# TakpadV6_1.net
KiCad netlist of a schematic drawn in EAGLE
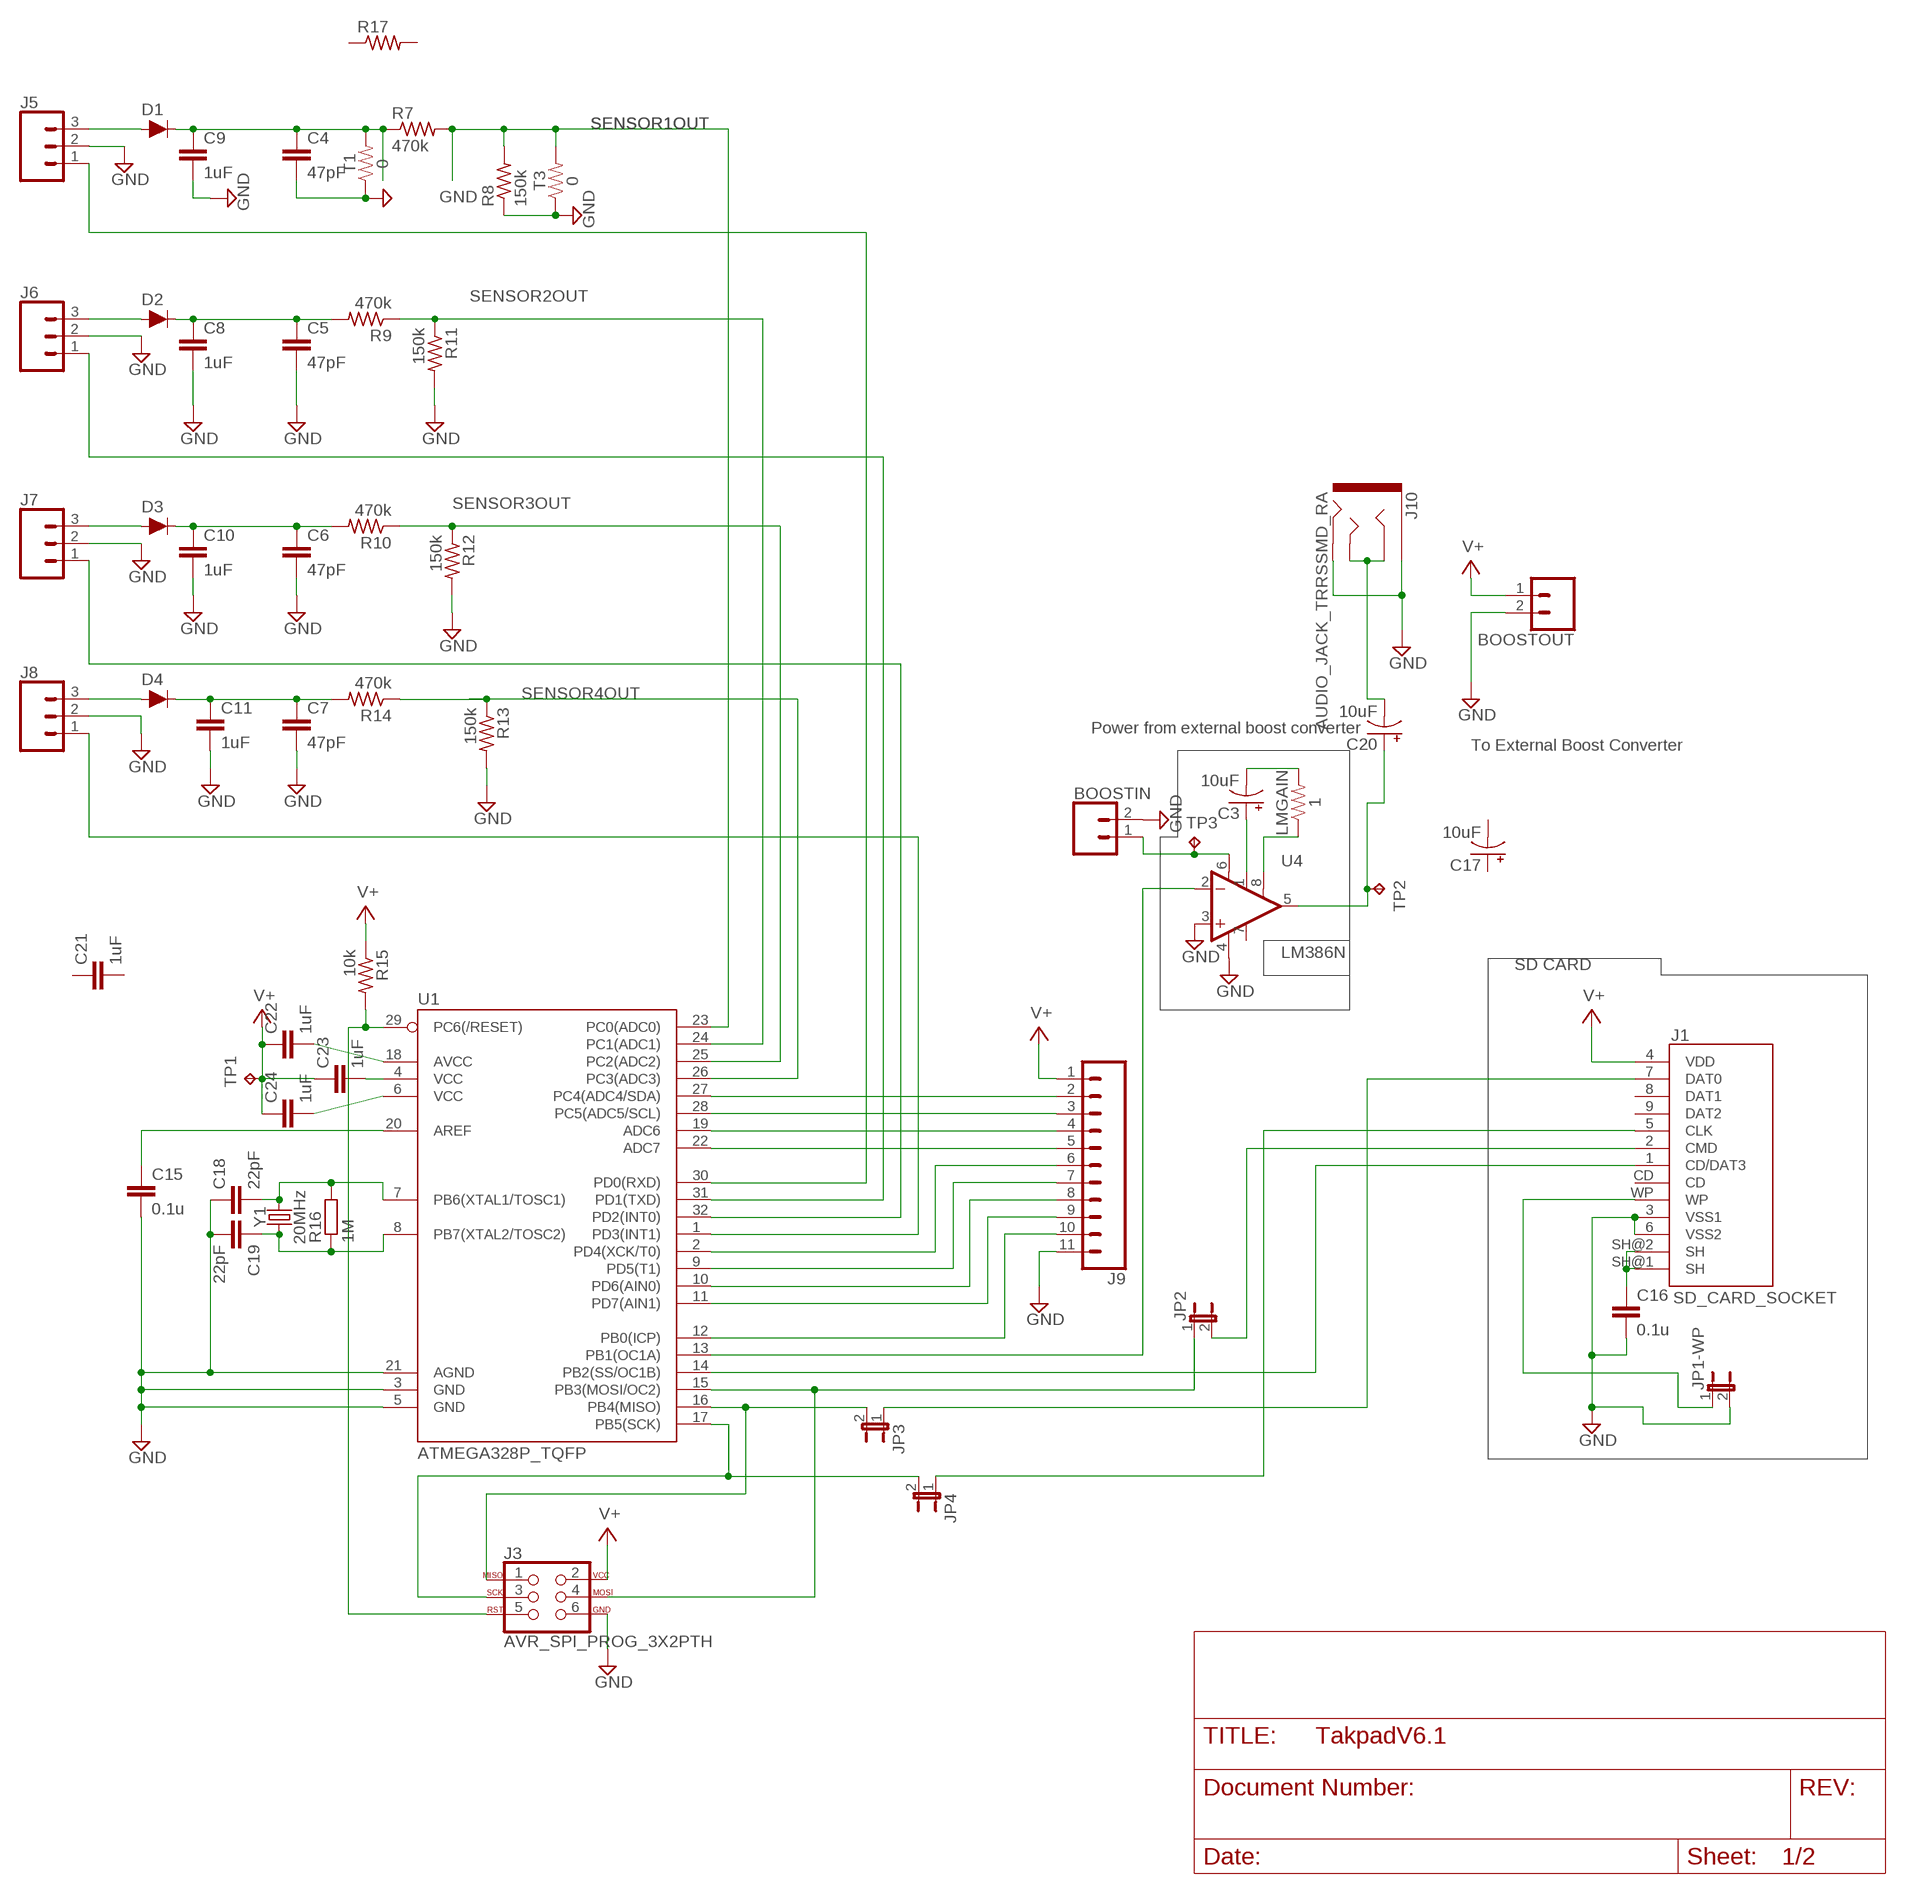
[diagram p0: schematic, sheet 1]
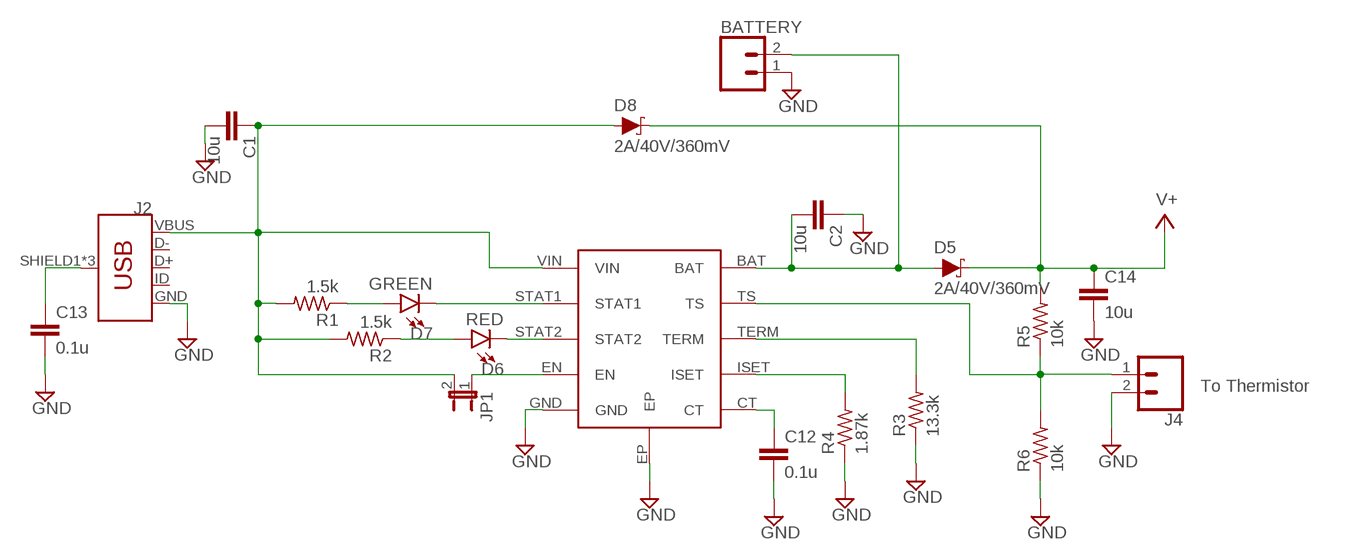
[diagram p1: schematic, sheet 2]

(export (version "E")
  (design (tool "Eeschema 10.0.6"))
  (components
    (comp (ref "BATTERY")
      (value "CONN_02")
      (footprint "eagle-import:1X02")
      (libsource (lib "eagle-import") (part "CONN_02"))
    )
    (comp (ref "C1")
      (value "10u")
      (footprint "eagle-import:C0402")
      (libsource (lib "eagle-import") (part "C-EUC0402"))
    )
    (comp (ref "C2")
      (value "10u")
      (footprint "eagle-import:C0402")
      (libsource (lib "eagle-import") (part "C-EUC0402"))
    )
    (comp (ref "C12")
      (value "0.1u")
      (footprint "eagle-import:C0402")
      (libsource (lib "eagle-import") (part "C-EUC0402"))
    )
    (comp (ref "C13")
      (value "0.1u")
      (footprint "eagle-import:C0402")
      (libsource (lib "eagle-import") (part "C-EUC0402"))
    )
    (comp (ref "C14")
      (value "10u")
      (footprint "eagle-import:C0402")
      (libsource (lib "eagle-import") (part "C-EUC0402"))
    )
    (comp (ref "D5")
      (value "2A/40V/360mV")
      (footprint "eagle-import:SMA-DIODE")
      (libsource (lib "eagle-import") (part "DIODE-SCHOTTKY-B340A"))
    )
    (comp (ref "D6")
      (value "RED")
      (footprint "eagle-import:LED-1206")
      (libsource (lib "eagle-import") (part "LED-RED1206"))
    )
    (comp (ref "D7")
      (value "GREEN")
      (footprint "eagle-import:LED-1206")
      (libsource (lib "eagle-import") (part "LED-GREEN1206"))
    )
    (comp (ref "D8")
      (value "2A/40V/360mV")
      (footprint "eagle-import:SMA-DIODE")
      (libsource (lib "eagle-import") (part "DIODE-SCHOTTKY-B340A"))
    )
    (comp (ref "J2")
      (value "USB_MICRO-BREDUCED_PASTE")
      (footprint "eagle-import:USB-B-MICRO-SMD_RED_PASTE")
      (libsource (lib "eagle-import") (part "USB_MICRO-BREDUCED_PASTE"))
    )
    (comp (ref "J4")
      (value "CONN_02")
      (footprint "eagle-import:1X02")
      (libsource (lib "eagle-import") (part "CONN_02"))
    )
    (comp (ref "JP1")
      (value "JUMPER-2PTH")
      (footprint "eagle-import:1X02")
      (libsource (lib "eagle-import") (part "JUMPER-2PTH"))
    )
    (comp (ref "R1")
      (value "1.5k")
      (footprint "eagle-import:M1206")
      (libsource (lib "eagle-import") (part "R-US_M1206"))
    )
    (comp (ref "R2")
      (value "1.5k")
      (footprint "eagle-import:M1206")
      (libsource (lib "eagle-import") (part "R-US_M1206"))
    )
    (comp (ref "R3")
      (value "13.3k")
      (footprint "eagle-import:M1206")
      (libsource (lib "eagle-import") (part "R-US_M1206"))
    )
    (comp (ref "R4")
      (value "1.87k")
      (footprint "eagle-import:M1206")
      (libsource (lib "eagle-import") (part "R-US_M1206"))
    )
    (comp (ref "R5")
      (value "10k")
      (footprint "eagle-import:M1206")
      (libsource (lib "eagle-import") (part "R-US_M1206"))
    )
    (comp (ref "R6")
      (value "10k")
      (footprint "eagle-import:M1206")
      (libsource (lib "eagle-import") (part "R-US_M1206"))
    )
    (comp (ref "U$1")
      (value "AAT3693")
      (footprint "eagle-import:IDH-AA-T1")
      (libsource (lib "eagle-import") (part "AAT3693"))
    )
    (comp (ref "BOOSTIN")
      (value "CONN_02")
      (footprint "eagle-import:1X02")
      (libsource (lib "eagle-import") (part "CONN_02"))
    )
    (comp (ref "BOOSTOUT")
      (value "CONN_02")
      (footprint "eagle-import:1X02")
      (libsource (lib "eagle-import") (part "CONN_02"))
    )
    (comp (ref "C3")
      (value "10uF")
      (footprint "eagle-import:CPOL-RADIAL-2.5MM-5MM-KIT")
      (libsource (lib "eagle-import") (part "10UF-POLAR-RADIAL-2.5MM-KIT-25V-20%"))
    )
    (comp (ref "C4")
      (value "47pF")
      (footprint "eagle-import:0603")
      (libsource (lib "eagle-import") (part "47PF-0603-50V-5%"))
    )
    (comp (ref "C5")
      (value "47pF")
      (footprint "eagle-import:0603")
      (libsource (lib "eagle-import") (part "47PF-0603-50V-5%"))
    )
    (comp (ref "C6")
      (value "47pF")
      (footprint "eagle-import:0603")
      (libsource (lib "eagle-import") (part "47PF-0603-50V-5%"))
    )
    (comp (ref "C7")
      (value "47pF")
      (footprint "eagle-import:0603")
      (libsource (lib "eagle-import") (part "47PF-0603-50V-5%"))
    )
    (comp (ref "C8")
      (value "1uF")
      (footprint "eagle-import:0603")
      (libsource (lib "eagle-import") (part "47PF-0603-50V-5%"))
    )
    (comp (ref "C9")
      (value "1uF")
      (footprint "eagle-import:0603")
      (libsource (lib "eagle-import") (part "47PF-0603-50V-5%"))
    )
    (comp (ref "C10")
      (value "1uF")
      (footprint "eagle-import:0603")
      (libsource (lib "eagle-import") (part "47PF-0603-50V-5%"))
    )
    (comp (ref "C11")
      (value "1uF")
      (footprint "eagle-import:0603")
      (libsource (lib "eagle-import") (part "47PF-0603-50V-5%"))
    )
    (comp (ref "C15")
      (value "0.1u")
      (footprint "eagle-import:C0402")
      (libsource (lib "eagle-import") (part "C-EUC0402"))
    )
    (comp (ref "C16")
      (value "0.1u")
      (footprint "eagle-import:C0402")
      (libsource (lib "eagle-import") (part "C-EUC0402"))
    )
    (comp (ref "C17")
      (value "10uF")
      (footprint "eagle-import:CPOL-RADIAL-2.5MM-5MM-KIT")
      (libsource (lib "eagle-import") (part "10UF-POLAR-RADIAL-2.5MM-KIT-25V-20%"))
    )
    (comp (ref "C18")
      (value "22pF")
      (footprint "eagle-import:C0402")
      (libsource (lib "eagle-import") (part "resistor_348_C-EUC0402"))
    )
    (comp (ref "C19")
      (value "22pF")
      (footprint "eagle-import:C0402")
      (libsource (lib "eagle-import") (part "resistor_348_C-EUC0402"))
    )
    (comp (ref "C20")
      (value "10uF")
      (footprint "eagle-import:CPOL-RADIAL-2.5MM-5MM-KIT")
      (libsource (lib "eagle-import") (part "10UF-POLAR-RADIAL-2.5MM-KIT-25V-20%"))
    )
    (comp (ref "C21")
      (value "1uF")
      (footprint "eagle-import:0603")
      (libsource (lib "eagle-import") (part "47PF-0603-50V-5%"))
    )
    (comp (ref "C22")
      (value "1uF")
      (footprint "eagle-import:0603")
      (libsource (lib "eagle-import") (part "47PF-0603-50V-5%"))
    )
    (comp (ref "C23")
      (value "1uF")
      (footprint "eagle-import:0603")
      (libsource (lib "eagle-import") (part "47PF-0603-50V-5%"))
    )
    (comp (ref "C24")
      (value "1uF")
      (footprint "eagle-import:0603")
      (libsource (lib "eagle-import") (part "47PF-0603-50V-5%"))
    )
    (comp (ref "D1")
      (value "200mA/100V/1V")
      (footprint "eagle-import:DIODE-1N4148")
      (libsource (lib "eagle-import") (part "DIODE-1N4148"))
    )
    (comp (ref "D2")
      (value "200mA/100V/1V")
      (footprint "eagle-import:DIODE-1N4148")
      (libsource (lib "eagle-import") (part "DIODE-1N4148"))
    )
    (comp (ref "D3")
      (value "200mA/100V/1V")
      (footprint "eagle-import:DIODE-1N4148")
      (libsource (lib "eagle-import") (part "DIODE-1N4148"))
    )
    (comp (ref "D4")
      (value "200mA/100V/1V")
      (footprint "eagle-import:DIODE-1N4148")
      (libsource (lib "eagle-import") (part "DIODE-1N4148"))
    )
    (comp (ref "J1")
      (value "SD_CARD_SOCKET")
      (footprint "eagle-import:SD")
      (libsource (lib "eagle-import") (part "SD_CARD_SOCKET"))
    )
    (comp (ref "J3")
      (value "AVR_SPI_PROG_3X2PTH")
      (footprint "eagle-import:2X3")
      (libsource (lib "eagle-import") (part "AVR_SPI_PROG_3X2PTH"))
    )
    (comp (ref "J5")
      (value "CONN_03")
      (footprint "eagle-import:1X03")
      (libsource (lib "eagle-import") (part "CONN_03"))
    )
    (comp (ref "J6")
      (value "CONN_03")
      (footprint "eagle-import:1X03")
      (libsource (lib "eagle-import") (part "CONN_03"))
    )
    (comp (ref "J7")
      (value "CONN_03")
      (footprint "eagle-import:1X03")
      (libsource (lib "eagle-import") (part "CONN_03"))
    )
    (comp (ref "J8")
      (value "CONN_03")
      (footprint "eagle-import:1X03")
      (libsource (lib "eagle-import") (part "CONN_03"))
    )
    (comp (ref "J9")
      (value "CONN_11")
      (footprint "eagle-import:1X11")
      (libsource (lib "eagle-import") (part "CONN_11"))
    )
    (comp (ref "J10")
      (value "AUDIO_JACK_TRRSSMD_RA")
      (footprint "eagle-import:AUDIO_JACK_3.5MM_TRRS_SMD_RA")
      (libsource (lib "eagle-import") (part "AUDIO_JACK_TRRSSMD_RA"))
    )
    (comp (ref "JP1-WP")
      (value "JUMPER-2PTH")
      (footprint "eagle-import:1X02")
      (libsource (lib "eagle-import") (part "JUMPER-2PTH"))
    )
    (comp (ref "JP2")
      (value "JUMPER-2PTH")
      (footprint "eagle-import:1X02")
      (libsource (lib "eagle-import") (part "JUMPER-2PTH"))
    )
    (comp (ref "JP3")
      (value "JUMPER-2PTH")
      (footprint "eagle-import:1X02")
      (libsource (lib "eagle-import") (part "JUMPER-2PTH"))
    )
    (comp (ref "JP4")
      (value "JUMPER-2PTH")
      (footprint "eagle-import:1X02")
      (libsource (lib "eagle-import") (part "JUMPER-2PTH"))
    )
    (comp (ref "LMGAIN")
      (value "1")
      (footprint "eagle-import:0603")
      (libsource (lib "eagle-import") (part "1OHM-0603-1/10W-1%"))
    )
    (comp (ref "R7")
      (value "470k")
      (footprint "eagle-import:M1206")
      (libsource (lib "eagle-import") (part "R-US_M1206"))
    )
    (comp (ref "R8")
      (value "150k")
      (footprint "eagle-import:M1206")
      (libsource (lib "eagle-import") (part "R-US_M1206"))
    )
    (comp (ref "R9")
      (value "470k")
      (footprint "eagle-import:M1206")
      (libsource (lib "eagle-import") (part "R-US_M1206"))
    )
    (comp (ref "R10")
      (value "470k")
      (footprint "eagle-import:M1206")
      (libsource (lib "eagle-import") (part "R-US_M1206"))
    )
    (comp (ref "R11")
      (value "150k")
      (footprint "eagle-import:M1206")
      (libsource (lib "eagle-import") (part "R-US_M1206"))
    )
    (comp (ref "R12")
      (value "150k")
      (footprint "eagle-import:M1206")
      (libsource (lib "eagle-import") (part "R-US_M1206"))
    )
    (comp (ref "R13")
      (value "150k")
      (footprint "eagle-import:M1206")
      (libsource (lib "eagle-import") (part "R-US_M1206"))
    )
    (comp (ref "R14")
      (value "470k")
      (footprint "eagle-import:M1206")
      (libsource (lib "eagle-import") (part "R-US_M1206"))
    )
    (comp (ref "R15")
      (value "10k")
      (footprint "eagle-import:M1206")
      (libsource (lib "eagle-import") (part "R-US_M1206"))
    )
    (comp (ref "R16")
      (value "1M")
      (footprint "eagle-import:R0402")
      (libsource (lib "eagle-import") (part "R-EU_R0402"))
    )
    (comp (ref "R17")
      (value "R-US_M1206")
      (footprint "eagle-import:M1206")
      (libsource (lib "eagle-import") (part "R-US_M1206"))
    )
    (comp (ref "T1")
      (value "0")
      (footprint "eagle-import:AXIAL-0.3")
      (libsource (lib "eagle-import") (part "1KOHM-HORIZ-1/4W-1%"))
    )
    (comp (ref "T3")
      (value "0")
      (footprint "eagle-import:AXIAL-0.3")
      (libsource (lib "eagle-import") (part "1KOHM-HORIZ-1/4W-1%"))
    )
    (comp (ref "TP1")
      (value "TPPAD1-17")
      (footprint "eagle-import:P1-17")
      (libsource (lib "eagle-import") (part "TPPAD1-17"))
    )
    (comp (ref "TP2")
      (value "TPPAD1-17")
      (footprint "eagle-import:P1-17")
      (libsource (lib "eagle-import") (part "TPPAD1-17"))
    )
    (comp (ref "TP3")
      (value "TPPAD1-17")
      (footprint "eagle-import:P1-17")
      (libsource (lib "eagle-import") (part "TPPAD1-17"))
    )
    (comp (ref "U1")
      (value "ATMEGA328P_TQFP")
      (footprint "eagle-import:TQFP32-08")
      (libsource (lib "eagle-import") (part "ATMEGA328P_TQFP"))
    )
    (comp (ref "U4")
      (value "LM386N")
      (footprint "eagle-import:DIP08")
      (libsource (lib "eagle-import") (part "LM386"))
    )
    (comp (ref "Y1")
      (value "20MHz")
      (footprint "eagle-import:HC49US")
      (libsource (lib "eagle-import") (part "CRYSTAL-16MHZPTH-HC49US"))
    )
  )
  (nets
    (net (code "1") (name "GND") (class "Default")
      (node (ref "BATTERY") (pin "1") (pinfunction "1_1") (pintype "passive"))
      (node (ref "BOOSTIN") (pin "2") (pinfunction "2_2") (pintype "passive"))
      (node (ref "BOOSTOUT") (pin "2") (pinfunction "2_2") (pintype "passive"))
      (node (ref "C1") (pin "2") (pinfunction "2_2") (pintype "passive"))
      (node (ref "C10") (pin "2") (pinfunction "2_2") (pintype "passive"))
      (node (ref "C11") (pin "2") (pinfunction "2_2") (pintype "passive"))
      (node (ref "C12") (pin "2") (pinfunction "2_2") (pintype "passive"))
      (node (ref "C13") (pin "2") (pinfunction "2_2") (pintype "passive"))
      (node (ref "C14") (pin "2") (pinfunction "2_2") (pintype "passive"))
      (node (ref "C15") (pin "2") (pinfunction "2_2") (pintype "passive"))
      (node (ref "C16") (pin "2") (pinfunction "2_2") (pintype "passive"))
      (node (ref "C18") (pin "1") (pinfunction "1_1") (pintype "passive"))
      (node (ref "C19") (pin "2") (pinfunction "2_2") (pintype "passive"))
      (node (ref "C2") (pin "1") (pinfunction "1_1") (pintype "passive"))
      (node (ref "C4") (pin "2") (pinfunction "2_2") (pintype "passive"))
      (node (ref "C5") (pin "2") (pinfunction "2_2") (pintype "passive"))
      (node (ref "C6") (pin "2") (pinfunction "2_2") (pintype "passive"))
      (node (ref "C7") (pin "2") (pinfunction "2_2") (pintype "passive"))
      (node (ref "C8") (pin "2") (pinfunction "2_2") (pintype "passive"))
      (node (ref "C9") (pin "2") (pinfunction "2_2") (pintype "passive"))
      (node (ref "J1") (pin "3") (pinfunction "VSS1_3") (pintype "power_in"))
      (node (ref "J1") (pin "6") (pinfunction "VSS2_6") (pintype "power_in"))
      (node (ref "J10") (pin "EARTH") (pinfunction "EARTH_EARTH") (pintype "bidirectional"))
      (node (ref "J10") (pin "RING2") (pinfunction "RING2_RING2") (pintype "bidirectional"))
      (node (ref "J2") (pin "GND") (pinfunction "GND_GND") (pintype "power_in"))
      (node (ref "J3") (pin "6") (pinfunction "6_6") (pintype "passive"))
      (node (ref "J4") (pin "2") (pinfunction "2_2") (pintype "passive"))
      (node (ref "J5") (pin "2") (pinfunction "2_2") (pintype "passive"))
      (node (ref "J6") (pin "2") (pinfunction "2_2") (pintype "passive"))
      (node (ref "J7") (pin "2") (pinfunction "2_2") (pintype "passive"))
      (node (ref "J8") (pin "2") (pinfunction "2_2") (pintype "passive"))
      (node (ref "J9") (pin "11") (pinfunction "11_11") (pintype "passive"))
      (node (ref "JP1-WP") (pin "2") (pinfunction "2_2") (pintype "passive"))
      (node (ref "R11") (pin "2") (pinfunction "2_2") (pintype "passive"))
      (node (ref "R12") (pin "2") (pinfunction "2_2") (pintype "passive"))
      (node (ref "R13") (pin "2") (pinfunction "2_2") (pintype "passive"))
      (node (ref "R3") (pin "1") (pinfunction "1_1") (pintype "passive"))
      (node (ref "R4") (pin "1") (pinfunction "1_1") (pintype "passive"))
      (node (ref "R6") (pin "1") (pinfunction "1_1") (pintype "passive"))
      (node (ref "R8") (pin "1") (pinfunction "1_1") (pintype "passive"))
      (node (ref "T1") (pin "P$1") (pinfunction "1_P$1") (pintype "passive"))
      (node (ref "T3") (pin "P$1") (pinfunction "1_P$1") (pintype "passive"))
      (node (ref "U$1") (pin "EP") (pinfunction "EP_EP") (pintype "bidirectional"))
      (node (ref "U$1") (pin "GND") (pinfunction "GND_GND") (pintype "bidirectional"))
      (node (ref "U1") (pin "21") (pinfunction "AGND_21") (pintype "bidirectional"))
      (node (ref "U1") (pin "3") (pinfunction "GND_3") (pintype "bidirectional"))
      (node (ref "U1") (pin "5") (pinfunction "GND_5") (pintype "bidirectional"))
      (node (ref "U4") (pin "3") (pinfunction "+IN_3") (pintype "input"))
      (node (ref "U4") (pin "4") (pinfunction "V-_4") (pintype "power_in"))
    )
    (net (code "2") (name "Net-(BATTERY-Pad2)") (class "Default")
      (node (ref "BATTERY") (pin "2") (pinfunction "2_2") (pintype "passive"))
      (node (ref "C2") (pin "2") (pinfunction "2_2") (pintype "passive"))
      (node (ref "D5") (pin "A") (pinfunction "A_A") (pintype "passive"))
      (node (ref "U$1") (pin "BAT") (pinfunction "BAT_BAT") (pintype "bidirectional"))
    )
    (net (code "3") (name "Net-(C1-Pad1)") (class "Default")
      (node (ref "C1") (pin "1") (pinfunction "1_1") (pintype "passive"))
      (node (ref "D8") (pin "A") (pinfunction "A_A") (pintype "passive"))
      (node (ref "J2") (pin "VBUS") (pinfunction "VBUS_VBUS") (pintype "power_in"))
      (node (ref "JP1") (pin "2") (pinfunction "2_2") (pintype "passive"))
      (node (ref "R1") (pin "2") (pinfunction "2_2") (pintype "passive"))
      (node (ref "R2") (pin "2") (pinfunction "2_2") (pintype "passive"))
      (node (ref "U$1") (pin "VIN") (pinfunction "VIN_VIN") (pintype "bidirectional"))
    )
    (net (code "4") (name "Net-(C3-+)") (class "Default")
      (node (ref "C3") (pin "1") (pinfunction "+_1") (pintype "passive"))
      (node (ref "U4") (pin "1") (pinfunction "GAIN_1") (pintype "bidirectional"))
    )
    (net (code "5") (name "Net-(C3--)") (class "Default")
      (node (ref "C3") (pin "2") (pinfunction "-_2") (pintype "passive"))
      (node (ref "LMGAIN") (pin "2") (pinfunction "2_2") (pintype "passive"))
    )
    (net (code "6") (name "Net-(C5-Pad1)") (class "Default")
      (node (ref "C5") (pin "1") (pinfunction "1_1") (pintype "passive"))
      (node (ref "C8") (pin "1") (pinfunction "1_1") (pintype "passive"))
      (node (ref "D2") (pin "C") (pinfunction "C_C") (pintype "passive"))
      (node (ref "R9") (pin "2") (pinfunction "2_2") (pintype "passive"))
    )
    (net (code "7") (name "Net-(C10-Pad1)") (class "Default")
      (node (ref "C10") (pin "1") (pinfunction "1_1") (pintype "passive"))
      (node (ref "C6") (pin "1") (pinfunction "1_1") (pintype "passive"))
      (node (ref "D3") (pin "C") (pinfunction "C_C") (pintype "passive"))
      (node (ref "R10") (pin "2") (pinfunction "2_2") (pintype "passive"))
    )
    (net (code "8") (name "Net-(C11-Pad1)") (class "Default")
      (node (ref "C11") (pin "1") (pinfunction "1_1") (pintype "passive"))
      (node (ref "C7") (pin "1") (pinfunction "1_1") (pintype "passive"))
      (node (ref "D4") (pin "C") (pinfunction "C_C") (pintype "passive"))
      (node (ref "R14") (pin "2") (pinfunction "2_2") (pintype "passive"))
    )
    (net (code "9") (name "Net-(C12-Pad1)") (class "Default")
      (node (ref "C12") (pin "1") (pinfunction "1_1") (pintype "passive"))
      (node (ref "U$1") (pin "CT") (pinfunction "CT_CT") (pintype "bidirectional"))
    )
    (net (code "10") (name "Net-(C13-Pad1)") (class "Default")
      (node (ref "C13") (pin "1") (pinfunction "1_1") (pintype "passive"))
      (node (ref "J2") (pin "SHIELD1") (pinfunction "SHIELD_SHIELD1") (pintype "bidirectional"))
      (node (ref "J2") (pin "SHIELD2") (pinfunction "SHIELD_SHIELD2") (pintype "bidirectional"))
      (node (ref "J2") (pin "SHIELD3") (pinfunction "SHIELD_SHIELD3") (pintype "bidirectional"))
    )
    (net (code "11") (name "Net-(C16-Pad1)") (class "Default")
      (node (ref "C16") (pin "1") (pinfunction "1_1") (pintype "passive"))
      (node (ref "J1") (pin "SH@1") (pinfunction "SH_SH@1") (pintype "bidirectional"))
      (node (ref "J1") (pin "SH@2") (pinfunction "SH_SH@2") (pintype "bidirectional"))
    )
    (net (code "12") (name "Net-(C20-+)") (class "Default")
      (node (ref "C20") (pin "1") (pinfunction "+_1") (pintype "passive"))
      (node (ref "TP2") (pin "TP") (pinfunction "TP_TP") (pintype "input"))
      (node (ref "U4") (pin "5") (pinfunction "OUT_5") (pintype "output"))
    )
    (net (code "13") (name "Net-(C20--)") (class "Default")
      (node (ref "C20") (pin "2") (pinfunction "-_2") (pintype "passive"))
      (node (ref "J10") (pin "RING1") (pinfunction "RING1_RING1") (pintype "bidirectional"))
      (node (ref "J10") (pin "TIP") (pinfunction "TIP_TIP") (pintype "bidirectional"))
    )
    (net (code "14") (name "Net-(C23-Pad2)") (class "Default")
      (node (ref "C23") (pin "2") (pinfunction "2_2") (pintype "passive"))
      (node (ref "U1") (pin "4") (pinfunction "VCC_4") (pintype "bidirectional"))
    )
    (net (code "15") (name "Net-(C24-Pad2)") (class "Default")
      (node (ref "C24") (pin "2") (pinfunction "2_2") (pintype "passive"))
      (node (ref "U1") (pin "6") (pinfunction "VCC_6") (pintype "bidirectional"))
    )
    (net (code "16") (name "Net-(D1-PadA)") (class "Default")
      (node (ref "D1") (pin "A") (pinfunction "A_A") (pintype "passive"))
      (node (ref "J5") (pin "3") (pinfunction "3_3") (pintype "passive"))
    )
    (net (code "17") (name "Net-(D2-PadA)") (class "Default")
      (node (ref "D2") (pin "A") (pinfunction "A_A") (pintype "passive"))
      (node (ref "J6") (pin "3") (pinfunction "3_3") (pintype "passive"))
    )
    (net (code "18") (name "Net-(D3-PadA)") (class "Default")
      (node (ref "D3") (pin "A") (pinfunction "A_A") (pintype "passive"))
      (node (ref "J7") (pin "3") (pinfunction "3_3") (pintype "passive"))
    )
    (net (code "19") (name "Net-(D4-PadA)") (class "Default")
      (node (ref "D4") (pin "A") (pinfunction "A_A") (pintype "passive"))
      (node (ref "J8") (pin "3") (pinfunction "3_3") (pintype "passive"))
    )
    (net (code "20") (name "Net-(D6-PadA)") (class "Default")
      (node (ref "D6") (pin "A") (pinfunction "A_A") (pintype "passive"))
      (node (ref "R2") (pin "1") (pinfunction "1_1") (pintype "passive"))
    )
    (net (code "21") (name "Net-(D6-PadC)") (class "Default")
      (node (ref "D6") (pin "C") (pinfunction "C_C") (pintype "passive"))
      (node (ref "U$1") (pin "STAT2") (pinfunction "STAT2_STAT2") (pintype "bidirectional"))
    )
    (net (code "22") (name "Net-(D7-PadA)") (class "Default")
      (node (ref "D7") (pin "A") (pinfunction "A_A") (pintype "passive"))
      (node (ref "R1") (pin "1") (pinfunction "1_1") (pintype "passive"))
    )
    (net (code "23") (name "Net-(D7-PadC)") (class "Default")
      (node (ref "D7") (pin "C") (pinfunction "C_C") (pintype "passive"))
      (node (ref "U$1") (pin "STAT1") (pinfunction "STAT1_STAT1") (pintype "bidirectional"))
    )
    (net (code "24") (name "Net-(J1-CD{slash}DAT3)") (class "Default")
      (node (ref "J1") (pin "1") (pinfunction "CD/DAT3_1") (pintype "bidirectional"))
      (node (ref "U1") (pin "14") (pinfunction "PB2(SS/OC1B)_14") (pintype "bidirectional"))
    )
    (net (code "25") (name "Net-(J1-CLK)") (class "Default")
      (node (ref "J1") (pin "5") (pinfunction "CLK_5") (pintype "bidirectional"))
      (node (ref "JP4") (pin "1") (pinfunction "1_1") (pintype "passive"))
    )
    (net (code "26") (name "Net-(J1-CMD)") (class "Default")
      (node (ref "J1") (pin "2") (pinfunction "CMD_2") (pintype "bidirectional"))
      (node (ref "JP2") (pin "2") (pinfunction "2_2") (pintype "passive"))
    )
    (net (code "27") (name "Net-(J1-DAT0)") (class "Default")
      (node (ref "J1") (pin "7") (pinfunction "DAT0_7") (pintype "bidirectional"))
      (node (ref "JP3") (pin "1") (pinfunction "1_1") (pintype "passive"))
    )
    (net (code "28") (name "Net-(J1-PadWP)") (class "Default")
      (node (ref "J1") (pin "WP") (pinfunction "WP_WP") (pintype "bidirectional"))
      (node (ref "JP1-WP") (pin "1") (pinfunction "1_1") (pintype "passive"))
    )
    (net (code "29") (name "Net-(J4-Pad1)") (class "Default")
      (node (ref "J4") (pin "1") (pinfunction "1_1") (pintype "passive"))
      (node (ref "R5") (pin "1") (pinfunction "1_1") (pintype "passive"))
      (node (ref "R6") (pin "2") (pinfunction "2_2") (pintype "passive"))
      (node (ref "U$1") (pin "TS") (pinfunction "TS_TS") (pintype "bidirectional"))
    )
    (net (code "30") (name "Net-(JP1-Pad1)") (class "Default")
      (node (ref "JP1") (pin "1") (pinfunction "1_1") (pintype "passive"))
      (node (ref "U$1") (pin "EN") (pinfunction "EN_EN") (pintype "bidirectional"))
    )
    (net (code "31") (name "Net-(LMGAIN-Pad1)") (class "Default")
      (node (ref "LMGAIN") (pin "1") (pinfunction "1_1") (pintype "passive"))
      (node (ref "U4") (pin "8") (pinfunction "GAIN_8") (pintype "bidirectional"))
    )
    (net (code "32") (name "Net-(R3-Pad2)") (class "Default")
      (node (ref "R3") (pin "2") (pinfunction "2_2") (pintype "passive"))
      (node (ref "U$1") (pin "TERM") (pinfunction "TERM_TERM") (pintype "bidirectional"))
    )
    (net (code "33") (name "Net-(R4-Pad2)") (class "Default")
      (node (ref "R4") (pin "2") (pinfunction "2_2") (pintype "passive"))
      (node (ref "U$1") (pin "ISET") (pinfunction "ISET_ISET") (pintype "bidirectional"))
    )
    (net (code "34") (name "Net-(T1-2)") (class "Default")
      (node (ref "C4") (pin "1") (pinfunction "1_1") (pintype "passive"))
      (node (ref "C9") (pin "1") (pinfunction "1_1") (pintype "passive"))
      (node (ref "D1") (pin "C") (pinfunction "C_C") (pintype "passive"))
      (node (ref "R7") (pin "1") (pinfunction "1_1") (pintype "passive"))
      (node (ref "T1") (pin "P$2") (pinfunction "2_P$2") (pintype "passive"))
    )
    (net (code "35") (name "Net-(U1-ADC6)") (class "Default")
      (node (ref "J9") (pin "4") (pinfunction "4_4") (pintype "passive"))
      (node (ref "U1") (pin "19") (pinfunction "ADC6_19") (pintype "bidirectional"))
    )
    (net (code "36") (name "Net-(U1-ADC7)") (class "Default")
      (node (ref "J9") (pin "5") (pinfunction "5_5") (pintype "passive"))
      (node (ref "U1") (pin "22") (pinfunction "ADC7_22") (pintype "bidirectional"))
    )
    (net (code "37") (name "Net-(U1-AREF)") (class "Default")
      (node (ref "C15") (pin "1") (pinfunction "1_1") (pintype "passive"))
      (node (ref "U1") (pin "20") (pinfunction "AREF_20") (pintype "bidirectional"))
    )
    (net (code "38") (name "Net-(U1-AVCC)") (class "Default")
      (node (ref "C22") (pin "2") (pinfunction "2_2") (pintype "passive"))
      (node (ref "U1") (pin "18") (pinfunction "AVCC_18") (pintype "bidirectional"))
    )
    (net (code "39") (name "Net-(U1-PB0(ICP))") (class "Default")
      (node (ref "J9") (pin "10") (pinfunction "10_10") (pintype "passive"))
      (node (ref "U1") (pin "12") (pinfunction "PB0(ICP)_12") (pintype "bidirectional"))
    )
    (net (code "40") (name "Net-(U1-PB1(OC1A))") (class "Default")
      (node (ref "U1") (pin "13") (pinfunction "PB1(OC1A)_13") (pintype "bidirectional"))
      (node (ref "U4") (pin "2") (pinfunction "-IN_2") (pintype "input"))
    )
    (net (code "41") (name "Net-(U1-PB3(MOSI{slash}OC2))") (class "Default")
      (node (ref "J3") (pin "4") (pinfunction "4_4") (pintype "passive"))
      (node (ref "JP2") (pin "1") (pinfunction "1_1") (pintype "passive"))
      (node (ref "U1") (pin "15") (pinfunction "PB3(MOSI/OC2)_15") (pintype "bidirectional"))
    )
    (net (code "42") (name "Net-(U1-PB4(MISO))") (class "Default")
      (node (ref "J3") (pin "1") (pinfunction "1_1") (pintype "passive"))
      (node (ref "JP3") (pin "2") (pinfunction "2_2") (pintype "passive"))
      (node (ref "U1") (pin "16") (pinfunction "PB4(MISO)_16") (pintype "bidirectional"))
    )
    (net (code "43") (name "Net-(U1-PB5(SCK))") (class "Default")
      (node (ref "J3") (pin "3") (pinfunction "3_3") (pintype "passive"))
      (node (ref "JP4") (pin "2") (pinfunction "2_2") (pintype "passive"))
      (node (ref "U1") (pin "17") (pinfunction "PB5(SCK)_17") (pintype "bidirectional"))
    )
    (net (code "44") (name "Net-(U1-PB6(XTAL1{slash}TOSC1))") (class "Default")
      (node (ref "C18") (pin "2") (pinfunction "2_2") (pintype "passive"))
      (node (ref "R16") (pin "2") (pinfunction "2_2") (pintype "passive"))
      (node (ref "U1") (pin "7") (pinfunction "PB6(XTAL1/TOSC1)_7") (pintype "bidirectional"))
      (node (ref "Y1") (pin "2") (pinfunction "2_2") (pintype "passive"))
    )
    (net (code "45") (name "Net-(U1-PB7(XTAL2{slash}TOSC2))") (class "Default")
      (node (ref "C19") (pin "1") (pinfunction "1_1") (pintype "passive"))
      (node (ref "R16") (pin "1") (pinfunction "1_1") (pintype "passive"))
      (node (ref "U1") (pin "8") (pinfunction "PB7(XTAL2/TOSC2)_8") (pintype "bidirectional"))
      (node (ref "Y1") (pin "1") (pinfunction "1_1") (pintype "passive"))
    )
    (net (code "46") (name "Net-(U1-PC4(ADC4{slash}SDA))") (class "Default")
      (node (ref "J9") (pin "2") (pinfunction "2_2") (pintype "passive"))
      (node (ref "U1") (pin "27") (pinfunction "PC4(ADC4/SDA)_27") (pintype "bidirectional"))
    )
    (net (code "47") (name "Net-(U1-PC5(ADC5{slash}SCL))") (class "Default")
      (node (ref "J9") (pin "3") (pinfunction "3_3") (pintype "passive"))
      (node (ref "U1") (pin "28") (pinfunction "PC5(ADC5/SCL)_28") (pintype "bidirectional"))
    )
    (net (code "48") (name "Net-(U1-PC6({slash}RESET))") (class "Default")
      (node (ref "J3") (pin "5") (pinfunction "5_5") (pintype "passive"))
      (node (ref "R15") (pin "2") (pinfunction "2_2") (pintype "passive"))
      (node (ref "U1") (pin "29") (pinfunction "PC6(/RESET)_29") (pintype "bidirectional"))
    )
    (net (code "49") (name "Net-(U1-PD0(RXD))") (class "Default")
      (node (ref "J5") (pin "1") (pinfunction "1_1") (pintype "passive"))
      (node (ref "U1") (pin "30") (pinfunction "PD0(RXD)_30") (pintype "bidirectional"))
    )
    (net (code "50") (name "Net-(U1-PD1(TXD))") (class "Default")
      (node (ref "J6") (pin "1") (pinfunction "1_1") (pintype "passive"))
      (node (ref "U1") (pin "31") (pinfunction "PD1(TXD)_31") (pintype "bidirectional"))
    )
    (net (code "51") (name "Net-(U1-PD2(INT0))") (class "Default")
      (node (ref "J7") (pin "1") (pinfunction "1_1") (pintype "passive"))
      (node (ref "U1") (pin "32") (pinfunction "PD2(INT0)_32") (pintype "bidirectional"))
    )
    (net (code "52") (name "Net-(U1-PD3(INT1))") (class "Default")
      (node (ref "J8") (pin "1") (pinfunction "1_1") (pintype "passive"))
      (node (ref "U1") (pin "1") (pinfunction "PD3(INT1)_1") (pintype "bidirectional"))
    )
    (net (code "53") (name "Net-(U1-PD4(XCK{slash}T0))") (class "Default")
      (node (ref "J9") (pin "6") (pinfunction "6_6") (pintype "passive"))
      (node (ref "U1") (pin "2") (pinfunction "PD4(XCK/T0)_2") (pintype "bidirectional"))
    )
    (net (code "54") (name "Net-(U1-PD5(T1))") (class "Default")
      (node (ref "J9") (pin "7") (pinfunction "7_7") (pintype "passive"))
      (node (ref "U1") (pin "9") (pinfunction "PD5(T1)_9") (pintype "bidirectional"))
    )
    (net (code "55") (name "Net-(U1-PD6(AIN0))") (class "Default")
      (node (ref "J9") (pin "8") (pinfunction "8_8") (pintype "passive"))
      (node (ref "U1") (pin "10") (pinfunction "PD6(AIN0)_10") (pintype "bidirectional"))
    )
    (net (code "56") (name "Net-(U1-PD7(AIN1))") (class "Default")
      (node (ref "J9") (pin "9") (pinfunction "9_9") (pintype "passive"))
      (node (ref "U1") (pin "11") (pinfunction "PD7(AIN1)_11") (pintype "bidirectional"))
    )
    (net (code "57") (name "Net-(U4-V+)") (class "Default")
      (node (ref "BOOSTIN") (pin "1") (pinfunction "1_1") (pintype "passive"))
      (node (ref "TP3") (pin "TP") (pinfunction "TP_TP") (pintype "input"))
      (node (ref "U4") (pin "6") (pinfunction "V+_6") (pintype "power_in"))
    )
    (net (code "58") (name "SENSOR1OUT") (class "Default")
      (node (ref "R7") (pin "2") (pinfunction "2_2") (pintype "passive"))
      (node (ref "R8") (pin "2") (pinfunction "2_2") (pintype "passive"))
      (node (ref "T3") (pin "P$2") (pinfunction "2_P$2") (pintype "passive"))
      (node (ref "U1") (pin "23") (pinfunction "PC0(ADC0)_23") (pintype "bidirectional"))
    )
    (net (code "59") (name "SENSOR2OUT") (class "Default")
      (node (ref "R11") (pin "1") (pinfunction "1_1") (pintype "passive"))
      (node (ref "R9") (pin "1") (pinfunction "1_1") (pintype "passive"))
      (node (ref "U1") (pin "24") (pinfunction "PC1(ADC1)_24") (pintype "bidirectional"))
    )
    (net (code "60") (name "SENSOR3OUT") (class "Default")
      (node (ref "R10") (pin "1") (pinfunction "1_1") (pintype "passive"))
      (node (ref "R12") (pin "1") (pinfunction "1_1") (pintype "passive"))
      (node (ref "U1") (pin "25") (pinfunction "PC2(ADC2)_25") (pintype "bidirectional"))
    )
    (net (code "61") (name "SENSOR4OUT") (class "Default")
      (node (ref "R13") (pin "1") (pinfunction "1_1") (pintype "passive"))
      (node (ref "R14") (pin "1") (pinfunction "1_1") (pintype "passive"))
      (node (ref "U1") (pin "26") (pinfunction "PC3(ADC3)_26") (pintype "bidirectional"))
    )
    (net (code "62") (name "V+") (class "Default")
      (node (ref "BOOSTOUT") (pin "1") (pinfunction "1_1") (pintype "passive"))
      (node (ref "C14") (pin "1") (pinfunction "1_1") (pintype "passive"))
      (node (ref "C22") (pin "1") (pinfunction "1_1") (pintype "passive"))
      (node (ref "C23") (pin "1") (pinfunction "1_1") (pintype "passive"))
      (node (ref "C24") (pin "1") (pinfunction "1_1") (pintype "passive"))
      (node (ref "D5") (pin "C") (pinfunction "C_C") (pintype "passive"))
      (node (ref "D8") (pin "C") (pinfunction "C_C") (pintype "passive"))
      (node (ref "J1") (pin "4") (pinfunction "VDD_4") (pintype "power_in"))
      (node (ref "J3") (pin "2") (pinfunction "2_2") (pintype "passive"))
      (node (ref "J9") (pin "1") (pinfunction "1_1") (pintype "passive"))
      (node (ref "R15") (pin "1") (pinfunction "1_1") (pintype "passive"))
      (node (ref "R5") (pin "2") (pinfunction "2_2") (pintype "passive"))
      (node (ref "TP1") (pin "TP") (pinfunction "TP_TP") (pintype "input"))
    )
    (net (code "63") (name "unconnected-(C17-+-Pad1)") (class "Default")
      (node (ref "C17") (pin "1") (pinfunction "+_1") (pintype "passive"))
    )
    (net (code "64") (name "unconnected-(C17---Pad2)") (class "Default")
      (node (ref "C17") (pin "2") (pinfunction "-_2") (pintype "passive"))
    )
    (net (code "65") (name "unconnected-(C21-Pad1)") (class "Default")
      (node (ref "C21") (pin "1") (pinfunction "1_1") (pintype "passive"))
    )
    (net (code "66") (name "unconnected-(C21-Pad2)") (class "Default")
      (node (ref "C21") (pin "2") (pinfunction "2_2") (pintype "passive"))
    )
    (net (code "67") (name "unconnected-(J1-DAT1-Pad8)") (class "Default")
      (node (ref "J1") (pin "8") (pinfunction "DAT1_8") (pintype "bidirectional"))
    )
    (net (code "68") (name "unconnected-(J1-DAT2-Pad9)") (class "Default")
      (node (ref "J1") (pin "9") (pinfunction "DAT2_9") (pintype "bidirectional"))
    )
    (net (code "69") (name "unconnected-(J1-PadCD)") (class "Default")
      (node (ref "J1") (pin "CD") (pinfunction "CD_CD") (pintype "bidirectional"))
    )
    (net (code "70") (name "unconnected-(J2-PadD+)") (class "Default")
      (node (ref "J2") (pin "D+") (pinfunction "D+_D+") (pintype "bidirectional"))
    )
    (net (code "71") (name "unconnected-(J2-PadD-)") (class "Default")
      (node (ref "J2") (pin "D-") (pinfunction "D-_D-") (pintype "bidirectional"))
    )
    (net (code "72") (name "unconnected-(J2-PadID)") (class "Default")
      (node (ref "J2") (pin "ID") (pinfunction "ID_ID") (pintype "bidirectional"))
    )
    (net (code "73") (name "unconnected-(R17-Pad1)") (class "Default")
      (node (ref "R17") (pin "1") (pinfunction "1_1") (pintype "passive"))
    )
    (net (code "74") (name "unconnected-(R17-Pad2)") (class "Default")
      (node (ref "R17") (pin "2") (pinfunction "2_2") (pintype "passive"))
    )
    (net (code "75") (name "unconnected-(U4-BP-Pad7)") (class "Default")
      (node (ref "U4") (pin "7") (pinfunction "BP_7") (pintype "bidirectional"))
    )
  )
)
